# Fri3D_2026_00.net
KiCad netlist of a schematic drawn in Altium Designer
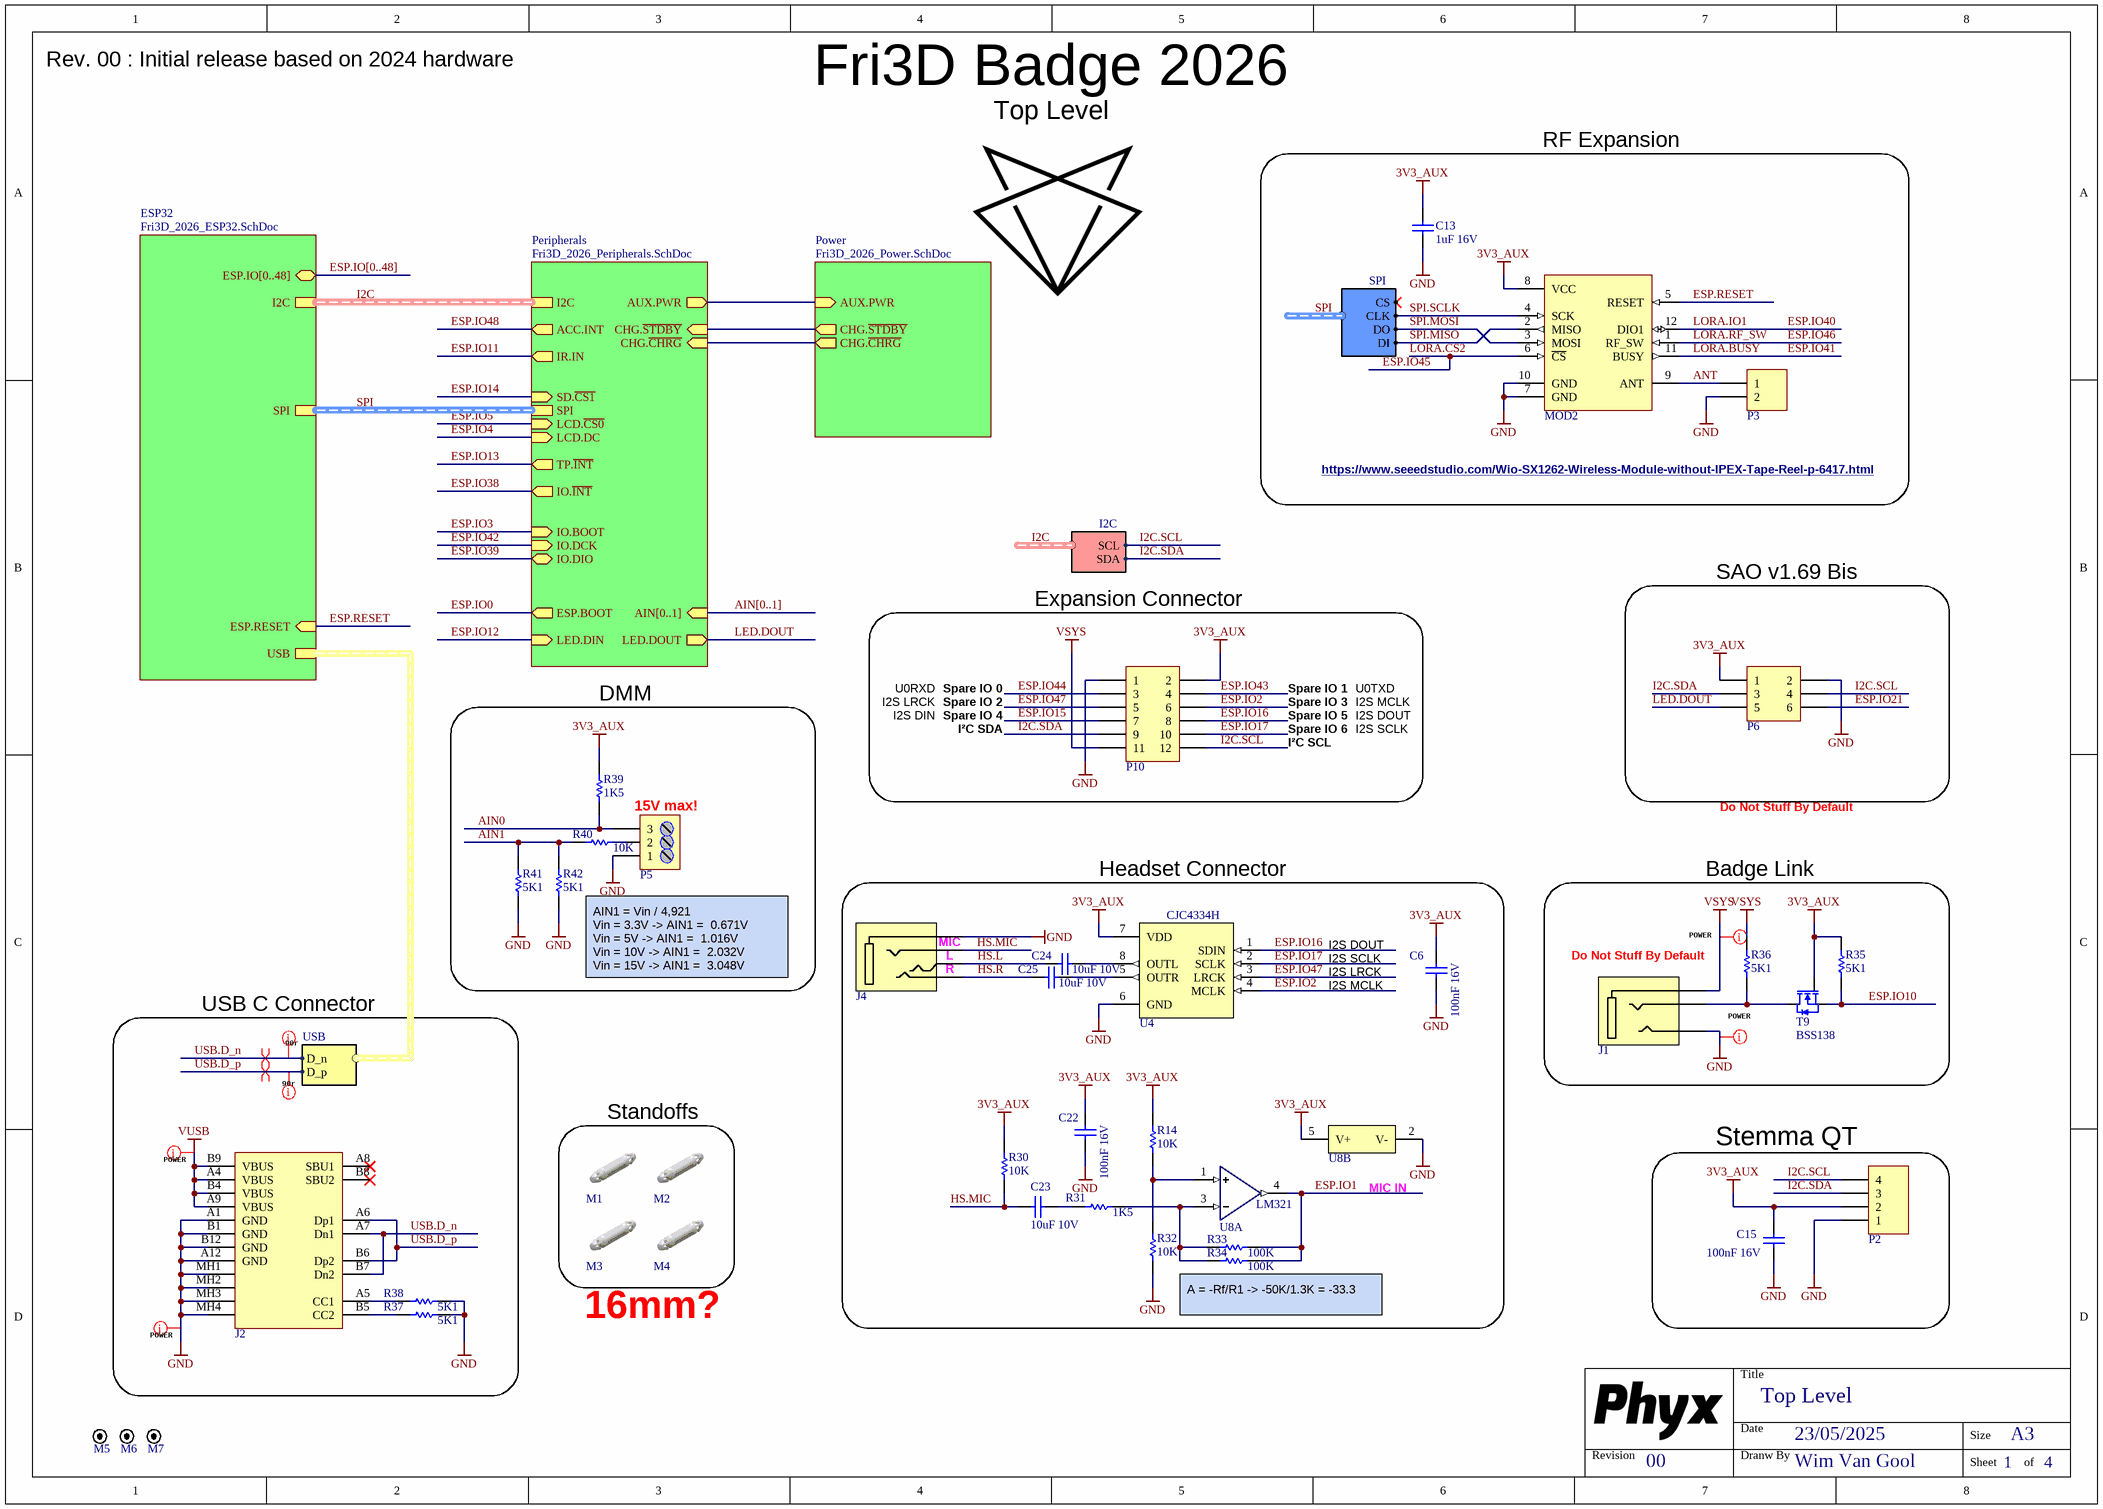
[diagram p0: Fri3D_2026_00.SchDoc]

(export (version "E")
  (design (tool "Eeschema 10.0.6"))
  (components
    (comp (ref "C6")
      (value "100nF 16V")
      (footprint "C0603_N")
      (description "Capacitor Ceramic")
      (libsource (lib "Phyx_Components") (part "CAP_CERAMIC"))
    )
    (comp (ref "C13")
      (value "1uF 16V")
      (footprint "C0603_N")
      (description "Capacitor Ceramic")
      (libsource (lib "Phyx_Components") (part "CAP_CERAMIC"))
    )
    (comp (ref "C15")
      (value "100nF 16V")
      (footprint "C0603_N")
      (description "Capacitor Ceramic")
      (libsource (lib "Phyx_Components") (part "CAP_CERAMIC"))
    )
    (comp (ref "C22")
      (value "100nF 16V")
      (footprint "C0603_N")
      (description "Capacitor Ceramic")
      (libsource (lib "Phyx_Components") (part "CAP_CERAMIC"))
    )
    (comp (ref "C23")
      (value "10uF 10V")
      (footprint "C0805_N")
      (description "Capacitor Ceramic")
      (libsource (lib "Phyx_Components") (part "CAP_CERAMIC"))
    )
    (comp (ref "C24")
      (value "10uF 10V")
      (footprint "C0805_N")
      (description "Capacitor Ceramic")
      (libsource (lib "Phyx_Components") (part "CAP_CERAMIC"))
    )
    (comp (ref "C25")
      (value "10uF 10V")
      (footprint "C0805_N")
      (description "Capacitor Ceramic")
      (libsource (lib "Phyx_Components") (part "CAP_CERAMIC"))
    )
    (comp (ref "J1")
      (value "3.5mm jack, black, 3 contacts")
      (footprint "SHOU_HAN_PJ-320A-3P")
      (description "=Description")
      (libsource (lib "Phyx_Components") (part "AUDIO_RST-123"))
    )
    (comp (ref "J2")
      (value "USB 2.0 C Reversible Receptacle Horizontal full SMD")
      (footprint "XUNPU-TYPEC-304S-ACP16")
      (libsource (lib "Phyx_Components") (part "USB_C_16_4"))
    )
    (comp (ref "J4")
      (value "3.5mm jack, black, 4 contacts")
      (footprint "HC-PJ-313E8-B-SMT")
      (description "=Description")
      (libsource (lib "Phyx_Components") (part "AUDIO_SRRT-1234"))
    )
    (comp (ref "M1")
      (value "HIWA LCC-12 Snap-in - Snap-in 12.7mm")
      (footprint "WE_709622400")
      (libsource (lib "Phyx_Components") (part "WE_SNSN"))
    )
    (comp (ref "M2")
      (value "HIWA LCC-12 Snap-in - Snap-in 12.7mm")
      (footprint "WE_709622400")
      (libsource (lib "Phyx_Components") (part "WE_SNSN"))
    )
    (comp (ref "M3")
      (value "HIWA LCC-12 Snap-in - Snap-in 12.7mm")
      (footprint "WE_709622400")
      (libsource (lib "Phyx_Components") (part "WE_SNSN"))
    )
    (comp (ref "M4")
      (value "HIWA LCC-12 Snap-in - Snap-in 12.7mm")
      (footprint "WE_709622400")
      (libsource (lib "Phyx_Components") (part "WE_SNSN"))
    )
    (comp (ref "M5")
      (value "Fiducial 0.5mm")
      (footprint "FID_0.5mm")
      (description "FIDUCIAL")
      (libsource (lib "Phyx_Components") (part "FIDUCIAL"))
    )
    (comp (ref "M6")
      (value "Fiducial 0.5mm")
      (footprint "FID_0.5mm")
      (description "FIDUCIAL")
      (libsource (lib "Phyx_Components") (part "FIDUCIAL"))
    )
    (comp (ref "M7")
      (value "Fiducial 0.5mm")
      (footprint "FID_0.5mm")
      (description "FIDUCIAL")
      (libsource (lib "Phyx_Components") (part "FIDUCIAL"))
    )
    (comp (ref "MOD2")
      (value "868/915MHz 22dBm LoRa Module with Antenna Pin")
      (footprint "SEE_Wio-SX1262")
      (description "=Description")
      (libsource (lib "Phyx_Components") (part "SEE_Wio-SX1262"))
    )
    (comp (ref "P2")
      (value "Header 1.0mm RA Shrouded 4")
      (footprint "WE_665104131822")
      (libsource (lib "Phyx_Components") (part "Header 4"))
    )
    (comp (ref "P3")
      (value "DEALON DL-SMA-K513-08K")
      (footprint "DEA_DL-SMA-K513-08K")
      (libsource (lib "Phyx_Components") (part "Header 2"))
    )
    (comp (ref "P5")
      (value "3 Way Screw HDR 3.5mm Rising Cage")
      (footprint "WE_691103110003")
      (libsource (lib "Phyx_Components") (part "TERM_BLCK_3"))
    )
    (comp (ref "P6")
      (value "Receptacle 3x2")
      (footprint "RCPT2X3")
      (libsource (lib "Phyx_Components") (part "Header 3X2"))
    )
    (comp (ref "P10")
      (value "Receptacle 6x2 SMD low profile")
      (footprint "WE_610312243021_POST")
      (libsource (lib "Phyx_Components") (part "Header 6X2"))
    )
    (comp (ref "R14")
      (value "10K")
      (footprint "R0603_N")
      (libsource (lib "Phyx_Components") (part "RESISTOR"))
    )
    (comp (ref "R30")
      (value "10K")
      (footprint "R0603_N")
      (libsource (lib "Phyx_Components") (part "RESISTOR"))
    )
    (comp (ref "R31")
      (value "1K5")
      (footprint "R0603_N")
      (libsource (lib "Phyx_Components") (part "RESISTOR"))
    )
    (comp (ref "R32")
      (value "10K")
      (footprint "R0603_N")
      (libsource (lib "Phyx_Components") (part "RESISTOR"))
    )
    (comp (ref "R33")
      (value "100K")
      (footprint "R0603_N")
      (libsource (lib "Phyx_Components") (part "RESISTOR"))
    )
    (comp (ref "R34")
      (value "100K")
      (footprint "R0603_N")
      (libsource (lib "Phyx_Components") (part "RESISTOR"))
    )
    (comp (ref "R35")
      (value "5K1")
      (footprint "R0603_N")
      (libsource (lib "Phyx_Components") (part "RESISTOR"))
    )
    (comp (ref "R36")
      (value "5K1")
      (footprint "R0603_N")
      (libsource (lib "Phyx_Components") (part "RESISTOR"))
    )
    (comp (ref "R37")
      (value "5K1")
      (footprint "R0603_N")
      (libsource (lib "Phyx_Components") (part "RESISTOR"))
    )
    (comp (ref "R38")
      (value "5K1")
      (footprint "R0603_N")
      (libsource (lib "Phyx_Components") (part "RESISTOR"))
    )
    (comp (ref "R39")
      (value "1K5")
      (footprint "R0603_N")
      (libsource (lib "Phyx_Components") (part "RESISTOR"))
    )
    (comp (ref "R40")
      (value "10K")
      (footprint "R0603_N")
      (libsource (lib "Phyx_Components") (part "RESISTOR"))
    )
    (comp (ref "R41")
      (value "5K1")
      (footprint "R0603_N")
      (libsource (lib "Phyx_Components") (part "RESISTOR"))
    )
    (comp (ref "R42")
      (value "5K1")
      (footprint "R0603_N")
      (libsource (lib "Phyx_Components") (part "RESISTOR"))
    )
    (comp (ref "T9")
      (value "BSS138")
      (footprint "SOT23-3")
      (fields (field (name "Comment") "0.2A N-Ch MOSFET Vgs 3.2"))
      (libsource (lib "Phyx_Components") (part "N_MOSFET_GSD"))
    )
    (comp (ref "U4")
      (value "CJC4334H")
      (footprint "SOIC_N_8")
      (description "I2S Stereo DAC with 24-Bit, 192 kHz Stereo D/A Converter")
      (fields (field (name "Comment") "I²S 24bit 192kHz 3V~3.6V DAC"))
      (libsource (lib "Phyx_Components") (part "CSC_CJC4334H"))
    )
    (comp (ref "U8")
      (value "LM321")
      (footprint "TI_DBV_R-PDSO-G5")
      (description "=Description")
      (fields (field (name "Comment") "Single, 30-V, 1-MHz operational amplifier"))
      (libsource (lib "Phyx_Components") (part "TI_LM321"))
    )
  )
  (nets
    (net (code "30") (name "/AIN0") (class "Default")
      (node (ref "P5") (pin "3") (pinfunction "3_3") (pintype "passive"))
      (node (ref "R39") (pin "1") (pinfunction "1_1") (pintype "passive"))
    )
    (net (code "31") (name "/AIN1") (class "Default")
      (node (ref "R40") (pin "1") (pinfunction "1_1") (pintype "passive"))
      (node (ref "R41") (pin "2") (pinfunction "2_2") (pintype "passive"))
      (node (ref "R42") (pin "2") (pinfunction "2_2") (pintype "passive"))
    )
    (net (code "33") (name "/ANT") (class "Default")
      (node (ref "MOD2") (pin "9") (pinfunction "ANT_9") (pintype "passive"))
      (node (ref "P3") (pin "1") (pinfunction "1_1") (pintype "passive"))
    )
    (net (code "38") (name "/ESP.IO1") (class "Default")
      (node (ref "R33") (pin "1") (pinfunction "1_1") (pintype "passive"))
      (node (ref "R34") (pin "1") (pinfunction "1_1") (pintype "passive"))
      (node (ref "U8") (pin "4") (pinfunction "OUT_4") (pintype "output"))
    )
    (net (code "39") (name "/ESP.IO2") (class "Default")
      (node (ref "P10") (pin "6") (pinfunction "6_6") (pintype "passive"))
      (node (ref "U4") (pin "4") (pinfunction "MCLK_4") (pintype "input"))
    )
    (net (code "43") (name "/ESP.IO10") (class "Default")
      (node (ref "R35") (pin "2") (pinfunction "2_2") (pintype "passive"))
      (node (ref "T9") (pin "2") (pinfunction "S_2") (pintype "passive"))
    )
    (net (code "48") (name "/ESP.IO15") (class "Default")
      (node (ref "P10") (pin "7") (pinfunction "7_7") (pintype "passive"))
    )
    (net (code "49") (name "/ESP.IO16") (class "Default")
      (node (ref "P10") (pin "8") (pinfunction "8_8") (pintype "passive"))
      (node (ref "U4") (pin "1") (pinfunction "SDIN_1") (pintype "input"))
    )
    (net (code "50") (name "/ESP.IO17") (class "Default")
      (node (ref "P10") (pin "10") (pinfunction "10_10") (pintype "passive"))
      (node (ref "U4") (pin "2") (pinfunction "SCLK_2") (pintype "input"))
    )
    (net (code "51") (name "/ESP.IO21") (class "Default")
      (node (ref "P6") (pin "6") (pinfunction "6_6") (pintype "passive"))
    )
    (net (code "54") (name "/ESP.IO40") (class "Default")
      (node (ref "MOD2") (pin "12") (pinfunction "DIO1_12") (pintype "bidirectional"))
    )
    (net (code "55") (name "/ESP.IO41") (class "Default")
      (node (ref "MOD2") (pin "11") (pinfunction "BUSY_11") (pintype "output"))
    )
    (net (code "57") (name "/ESP.IO43") (class "Default")
      (node (ref "P10") (pin "4") (pinfunction "4_4") (pintype "passive"))
    )
    (net (code "58") (name "/ESP.IO44") (class "Default")
      (node (ref "P10") (pin "3") (pinfunction "3_3") (pintype "passive"))
    )
    (net (code "59") (name "/ESP.IO45") (class "Default")
      (node (ref "MOD2") (pin "6") (pinfunction "~{CS}_6") (pintype "input"))
    )
    (net (code "60") (name "/ESP.IO46") (class "Default")
      (node (ref "MOD2") (pin "1") (pinfunction "RF_SW_1") (pintype "input"))
    )
    (net (code "61") (name "/ESP.IO47") (class "Default")
      (node (ref "P10") (pin "5") (pinfunction "5_5") (pintype "passive"))
      (node (ref "U4") (pin "3") (pinfunction "LRCK_3") (pintype "input"))
    )
    (net (code "64") (name "/ESP.RESET") (class "Default")
      (node (ref "MOD2") (pin "5") (pinfunction "RESET_5") (pintype "input"))
    )
    (net (code "65") (name "/HS.L") (class "Default")
      (node (ref "C24") (pin "1") (pinfunction "1_1") (pintype "passive"))
      (node (ref "J4") (pin "4") (pinfunction "Tip_4") (pintype "passive"))
    )
    (net (code "66") (name "/HS.MIC") (class "Default")
      (node (ref "C23") (pin "1") (pinfunction "1_1") (pintype "passive"))
      (node (ref "J4") (pin "2") (pinfunction "Ring_2") (pintype "passive"))
      (node (ref "R30") (pin "2") (pinfunction "2_2") (pintype "passive"))
    )
    (net (code "67") (name "/HS.R") (class "Default")
      (node (ref "C25") (pin "1") (pinfunction "1_1") (pintype "passive"))
      (node (ref "J4") (pin "3") (pinfunction "Ring_3") (pintype "passive"))
    )
    (net (code "68") (name "/I2C.SCL") (class "Default")
      (node (ref "P10") (pin "12") (pinfunction "12_12") (pintype "passive"))
      (node (ref "P2") (pin "4") (pinfunction "4_4") (pintype "passive"))
      (node (ref "P6") (pin "4") (pinfunction "4_4") (pintype "passive"))
    )
    (net (code "69") (name "/I2C.SDA") (class "Default")
      (node (ref "P10") (pin "9") (pinfunction "9_9") (pintype "passive"))
      (node (ref "P2") (pin "3") (pinfunction "3_3") (pintype "passive"))
      (node (ref "P6") (pin "3") (pinfunction "3_3") (pintype "passive"))
    )
    (net (code "71") (name "/LED.DOUT") (class "Default")
      (node (ref "P6") (pin "5") (pinfunction "5_5") (pintype "passive"))
    )
    (net (code "72") (name "/SPI.MISO") (class "Default")
      (node (ref "MOD2") (pin "2") (pinfunction "MISO_2") (pintype "output"))
    )
    (net (code "73") (name "/SPI.MOSI") (class "Default")
      (node (ref "MOD2") (pin "3") (pinfunction "MOSI_3") (pintype "input"))
    )
    (net (code "74") (name "/SPI.SCLK") (class "Default")
      (node (ref "MOD2") (pin "4") (pinfunction "SCK_4") (pintype "input"))
    )
    (net (code "76") (name "/USB.D_n") (class "Default")
      (node (ref "J2") (pin "A7") (pinfunction "Dn1_A7") (pintype "passive"))
      (node (ref "J2") (pin "B7") (pinfunction "Dn2_B7") (pintype "passive"))
    )
    (net (code "77") (name "/USB.D_p") (class "Default")
      (node (ref "J2") (pin "A6") (pinfunction "Dp1_A6") (pintype "passive"))
      (node (ref "J2") (pin "B6") (pinfunction "Dp2_B6") (pintype "passive"))
    )
    (net (code "81") (name "3V3_AUX") (class "Default")
      (node (ref "C13") (pin "1") (pinfunction "1_1") (pintype "passive"))
      (node (ref "C15") (pin "1") (pinfunction "1_1") (pintype "passive"))
      (node (ref "C22") (pin "1") (pinfunction "1_1") (pintype "passive"))
      (node (ref "C6") (pin "1") (pinfunction "1_1") (pintype "passive"))
      (node (ref "MOD2") (pin "8") (pinfunction "VCC_8") (pintype "power_in"))
      (node (ref "P10") (pin "2") (pinfunction "2_2") (pintype "passive"))
      (node (ref "P2") (pin "2") (pinfunction "2_2") (pintype "passive"))
      (node (ref "P6") (pin "1") (pinfunction "1_1") (pintype "passive"))
      (node (ref "R14") (pin "1") (pinfunction "1_1") (pintype "passive"))
      (node (ref "R30") (pin "1") (pinfunction "1_1") (pintype "passive"))
      (node (ref "R35") (pin "1") (pinfunction "1_1") (pintype "passive"))
      (node (ref "R39") (pin "2") (pinfunction "2_2") (pintype "passive"))
      (node (ref "T9") (pin "1") (pinfunction "G_1") (pintype "passive"))
      (node (ref "U4") (pin "7") (pinfunction "VDD_7") (pintype "power_in"))
      (node (ref "U8") (pin "5") (pinfunction "V+_5") (pintype "power_in"))
    )
    (net (code "82") (name "GND") (class "Default")
      (node (ref "C13") (pin "2") (pinfunction "2_2") (pintype "passive"))
      (node (ref "C15") (pin "2") (pinfunction "2_2") (pintype "passive"))
      (node (ref "C22") (pin "2") (pinfunction "2_2") (pintype "passive"))
      (node (ref "C6") (pin "2") (pinfunction "2_2") (pintype "passive"))
      (node (ref "J1") (pin "2") (pinfunction "Tip_2") (pintype "passive"))
      (node (ref "J2") (pin "A1") (pinfunction "GND_A1") (pintype "passive"))
      (node (ref "J2") (pin "A12") (pinfunction "GND_A12") (pintype "passive"))
      (node (ref "J2") (pin "B1") (pinfunction "GND_B1") (pintype "passive"))
      (node (ref "J2") (pin "B12") (pinfunction "GND_B12") (pintype "passive"))
      (node (ref "J2") (pin "MH1") (pinfunction "Tab_MH1") (pintype "passive"))
      (node (ref "J2") (pin "MH2") (pinfunction "Tab_MH2") (pintype "passive"))
      (node (ref "J2") (pin "MH3") (pinfunction "Tab_MH3") (pintype "passive"))
      (node (ref "J2") (pin "MH4") (pinfunction "Tab_MH4") (pintype "passive"))
      (node (ref "J4") (pin "1") (pinfunction "Sleeve_1") (pintype "passive"))
      (node (ref "MOD2") (pin "10") (pinfunction "GND_10") (pintype "power_in"))
      (node (ref "MOD2") (pin "7") (pinfunction "GND_7") (pintype "power_in"))
      (node (ref "P10") (pin "1") (pinfunction "1_1") (pintype "passive"))
      (node (ref "P2") (pin "1") (pinfunction "1_1") (pintype "passive"))
      (node (ref "P3") (pin "2") (pinfunction "2_2") (pintype "passive"))
      (node (ref "P5") (pin "1") (pinfunction "1_1") (pintype "passive"))
      (node (ref "P6") (pin "2") (pinfunction "2_2") (pintype "passive"))
      (node (ref "R32") (pin "2") (pinfunction "2_2") (pintype "passive"))
      (node (ref "R37") (pin "2") (pinfunction "2_2") (pintype "passive"))
      (node (ref "R38") (pin "2") (pinfunction "2_2") (pintype "passive"))
      (node (ref "R41") (pin "1") (pinfunction "1_1") (pintype "passive"))
      (node (ref "R42") (pin "1") (pinfunction "1_1") (pintype "passive"))
      (node (ref "U4") (pin "6") (pinfunction "GND_6") (pintype "power_in"))
      (node (ref "U8") (pin "2") (pinfunction "V-_2") (pintype "power_in"))
    )
    (net (code "83") (name "Net-(C23-Pad2)") (class "Default")
      (node (ref "C23") (pin "2") (pinfunction "2_2") (pintype "passive"))
      (node (ref "R31") (pin "2") (pinfunction "2_2") (pintype "passive"))
    )
    (net (code "84") (name "Net-(J1-Ring)") (class "Default")
      (node (ref "J1") (pin "3") (pinfunction "Ring_3") (pintype "passive"))
      (node (ref "R36") (pin "2") (pinfunction "2_2") (pintype "passive"))
      (node (ref "T9") (pin "3") (pinfunction "D_3") (pintype "passive"))
    )
    (net (code "85") (name "Net-(J2-CC1)") (class "Default")
      (node (ref "J2") (pin "A5") (pinfunction "CC1_A5") (pintype "passive"))
      (node (ref "R38") (pin "1") (pinfunction "1_1") (pintype "passive"))
    )
    (net (code "86") (name "Net-(J2-CC2)") (class "Default")
      (node (ref "J2") (pin "B5") (pinfunction "CC2_B5") (pintype "passive"))
      (node (ref "R37") (pin "1") (pinfunction "1_1") (pintype "passive"))
    )
    (net (code "87") (name "Net-(P5-Pad2)") (class "Default")
      (node (ref "P5") (pin "2") (pinfunction "2_2") (pintype "passive"))
      (node (ref "R40") (pin "2") (pinfunction "2_2") (pintype "passive"))
    )
    (net (code "88") (name "Net-(U4-OUTL)") (class "Default")
      (node (ref "C24") (pin "2") (pinfunction "2_2") (pintype "passive"))
      (node (ref "U4") (pin "8") (pinfunction "OUTL_8") (pintype "output"))
    )
    (net (code "89") (name "Net-(U4-OUTR)") (class "Default")
      (node (ref "C25") (pin "2") (pinfunction "2_2") (pintype "passive"))
      (node (ref "U4") (pin "5") (pinfunction "OUTR_5") (pintype "output"))
    )
    (net (code "90") (name "Net-(U8A-+)") (class "Default")
      (node (ref "R14") (pin "2") (pinfunction "2_2") (pintype "passive"))
      (node (ref "R32") (pin "1") (pinfunction "1_1") (pintype "passive"))
      (node (ref "U8") (pin "1") (pinfunction "+_1") (pintype "input"))
    )
    (net (code "91") (name "Net-(U8A--)") (class "Default")
      (node (ref "R31") (pin "1") (pinfunction "1_1") (pintype "passive"))
      (node (ref "R33") (pin "2") (pinfunction "2_2") (pintype "passive"))
      (node (ref "R34") (pin "2") (pinfunction "2_2") (pintype "passive"))
      (node (ref "U8") (pin "3") (pinfunction "-_3") (pintype "input"))
    )
    (net (code "92") (name "VSYS") (class "Default")
      (node (ref "J1") (pin "1") (pinfunction "Sleeve_1") (pintype "passive"))
      (node (ref "P10") (pin "11") (pinfunction "11_11") (pintype "passive"))
      (node (ref "R36") (pin "1") (pinfunction "1_1") (pintype "passive"))
    )
    (net (code "93") (name "VUSB") (class "Default")
      (node (ref "J2") (pin "A4") (pinfunction "VBUS_A4") (pintype "passive"))
      (node (ref "J2") (pin "A9") (pinfunction "VBUS_A9") (pintype "passive"))
      (node (ref "J2") (pin "B4") (pinfunction "VBUS_B4") (pintype "passive"))
      (node (ref "J2") (pin "B9") (pinfunction "VBUS_B9") (pintype "passive"))
    )
    (net (code "94") (name "unconnected-(J2-SBU1-PadA8)") (class "Default")
      (node (ref "J2") (pin "A8") (pinfunction "SBU1_A8") (pintype "passive+no_connect"))
    )
    (net (code "95") (name "unconnected-(J2-SBU2-PadB8)") (class "Default")
      (node (ref "J2") (pin "B8") (pinfunction "SBU2_B8") (pintype "passive+no_connect"))
    )
  )
)
